# Me-RJ11_Adapter_v2_0.net
KiCad netlist of a schematic drawn in EAGLE
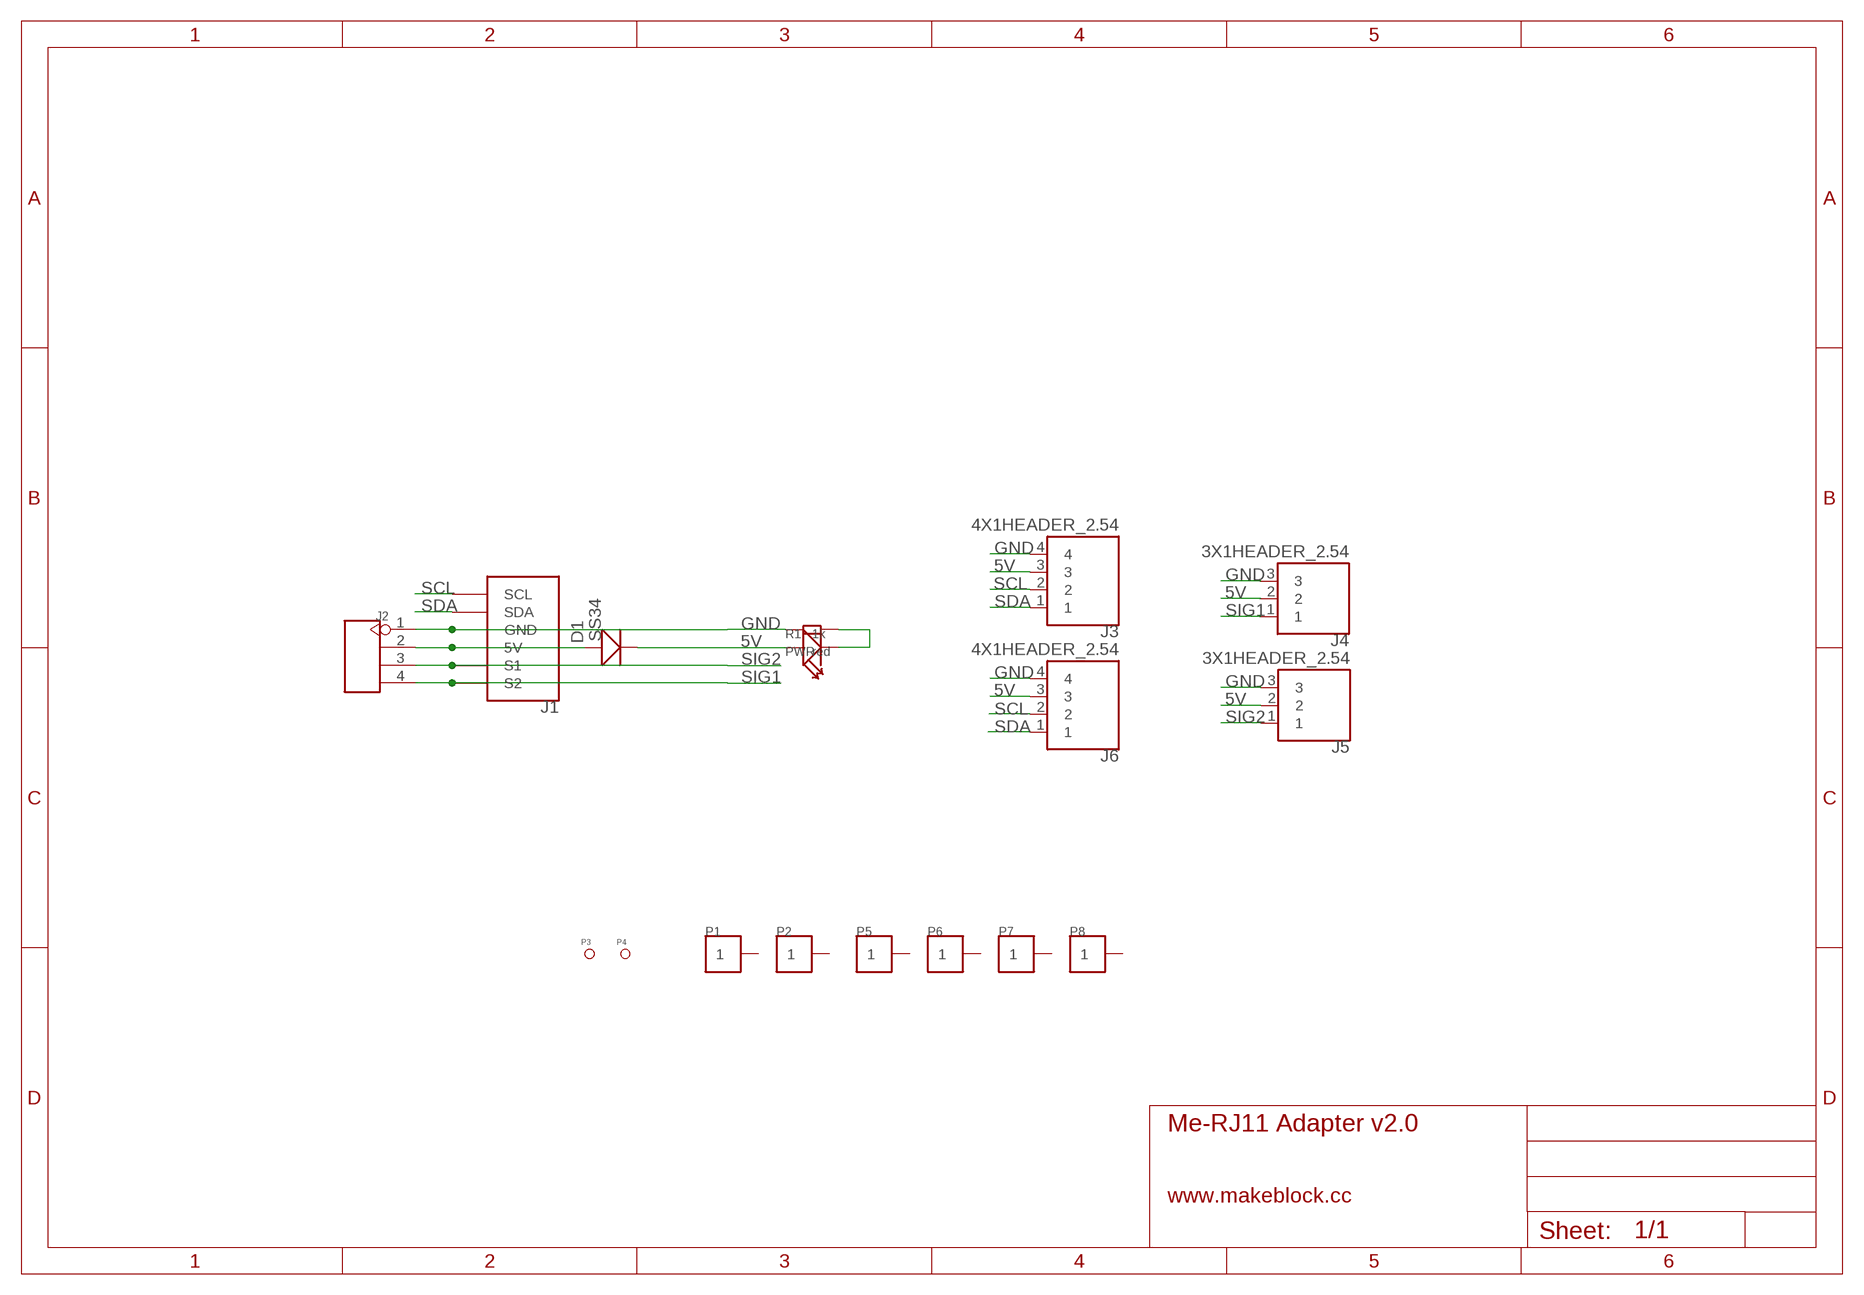
[diagram p0: schematic, sheet 1]

(export (version "E")
  (design (tool "Eeschema 10.0.6"))
  (components
    (comp (ref "D1")
      (value "SS34")
      (footprint "eagle-import:D2010")
      (libsource (lib "eagle-import") (part "D'SMA'"))
    )
    (comp (ref "J1")
      (value "RJ11-6P6C-DIGI")
      (footprint "eagle-import:RJ11-6P6C")
      (libsource (lib "eagle-import") (part "RJ11-6P6C-DIGI"))
    )
    (comp (ref "J2")
      (value "HEADER-4P-60/35MIL")
      (footprint "eagle-import:4P-65_35MIL")
      (libsource (lib "eagle-import") (part "HEADER-4P-60/35MIL"))
    )
    (comp (ref "J3")
      (value "4X1HEADER_2.54")
      (footprint "eagle-import:4X1HEADER_2.54")
      (libsource (lib "eagle-import") (part "4X1HEADER_2.54"))
    )
    (comp (ref "J4")
      (value "3X1HEADER_2.54")
      (footprint "eagle-import:3X1HEADER_2.54")
      (libsource (lib "eagle-import") (part "3X1HEADER_2.54"))
    )
    (comp (ref "J5")
      (value "3X1HEADER_2.54")
      (footprint "eagle-import:3X1HEADER_2.54")
      (libsource (lib "eagle-import") (part "3X1HEADER_2.54"))
    )
    (comp (ref "J6")
      (value "4X1HEADER_2.54")
      (footprint "eagle-import:4X1HEADER_2.54")
      (libsource (lib "eagle-import") (part "4X1HEADER_2.54"))
    )
    (comp (ref "P1")
      (value "PAD-1P-4MM")
      (footprint "eagle-import:HOLE-01")
      (libsource (lib "eagle-import") (part "PAD-1P-4MM"))
    )
    (comp (ref "P2")
      (value "PAD-1P-4MM")
      (footprint "eagle-import:HOLE-01")
      (libsource (lib "eagle-import") (part "PAD-1P-4MM"))
    )
    (comp (ref "P3")
      (value "PAD-MARK")
      (footprint "eagle-import:ROUND-MARK-1.0")
      (fields (field (name "PARTNO") "DNP"))
      (libsource (lib "eagle-import") (part "PAD-MARK"))
    )
    (comp (ref "P4")
      (value "PAD-MARK")
      (footprint "eagle-import:ROUND-MARK-1.0")
      (fields (field (name "PARTNO") "DNP"))
      (libsource (lib "eagle-import") (part "PAD-MARK"))
    )
    (comp (ref "P5")
      (value "PAD-1P-4MM")
      (footprint "eagle-import:HOLE-01")
      (libsource (lib "eagle-import") (part "PAD-1P-4MM"))
    )
    (comp (ref "P6")
      (value "PAD-1P-4MM")
      (footprint "eagle-import:HOLE-01")
      (libsource (lib "eagle-import") (part "PAD-1P-4MM"))
    )
    (comp (ref "P7")
      (value "PAD-1P-4MM")
      (footprint "eagle-import:HOLE-01")
      (libsource (lib "eagle-import") (part "PAD-1P-4MM"))
    )
    (comp (ref "P8")
      (value "PAD-1P-4MM")
      (footprint "eagle-import:HOLE-01")
      (libsource (lib "eagle-import") (part "PAD-1P-4MM"))
    )
    (comp (ref "PWR")
      (value "red")
      (footprint "eagle-import:LED-0603")
      (libsource (lib "eagle-import") (part "LED'0603'"))
    )
    (comp (ref "R1")
      (value "1k")
      (footprint "eagle-import:0603")
      (libsource (lib "eagle-import") (part "R-0603"))
    )
  )
  (nets
    (net (code "1") (name "/5V") (class "Default")
      (node (ref "D1") (pin "-") (pinfunction "-_-") (pintype "passive"))
      (node (ref "J3") (pin "3") (pinfunction "3_3") (pintype "bidirectional"))
      (node (ref "J4") (pin "2") (pinfunction "2_2") (pintype "bidirectional"))
      (node (ref "J5") (pin "2") (pinfunction "2_2") (pintype "bidirectional"))
      (node (ref "J6") (pin "3") (pinfunction "3_3") (pintype "bidirectional"))
      (node (ref "PWR") (pin "+") (pinfunction "+_+") (pintype "passive"))
    )
    (net (code "2") (name "/GND") (class "Default")
      (node (ref "J1") (pin "3") (pinfunction "GND_3") (pintype "bidirectional"))
      (node (ref "J2") (pin "1") (pinfunction "P$1_1") (pintype "bidirectional"))
      (node (ref "J3") (pin "4") (pinfunction "4_4") (pintype "bidirectional"))
      (node (ref "J4") (pin "3") (pinfunction "3_3") (pintype "bidirectional"))
      (node (ref "J5") (pin "3") (pinfunction "3_3") (pintype "bidirectional"))
      (node (ref "J6") (pin "4") (pinfunction "4_4") (pintype "bidirectional"))
      (node (ref "R1") (pin "1") (pinfunction "1_1") (pintype "passive"))
    )
    (net (code "3") (name "/SCL") (class "Default")
      (node (ref "J1") (pin "1") (pinfunction "SCL_1") (pintype "bidirectional"))
      (node (ref "J3") (pin "2") (pinfunction "2_2") (pintype "bidirectional"))
      (node (ref "J6") (pin "2") (pinfunction "2_2") (pintype "bidirectional"))
    )
    (net (code "4") (name "/SDA") (class "Default")
      (node (ref "J1") (pin "2") (pinfunction "SDA_2") (pintype "bidirectional"))
      (node (ref "J3") (pin "1") (pinfunction "1_1") (pintype "bidirectional"))
      (node (ref "J6") (pin "1") (pinfunction "1_1") (pintype "bidirectional"))
    )
    (net (code "5") (name "/SIG1") (class "Default")
      (node (ref "J1") (pin "6") (pinfunction "S2_6") (pintype "bidirectional"))
      (node (ref "J2") (pin "4") (pinfunction "P$4_4") (pintype "bidirectional"))
      (node (ref "J4") (pin "1") (pinfunction "1_1") (pintype "bidirectional"))
    )
    (net (code "6") (name "/SIG2") (class "Default")
      (node (ref "J1") (pin "5") (pinfunction "S1_5") (pintype "bidirectional"))
      (node (ref "J2") (pin "3") (pinfunction "P$3_3") (pintype "bidirectional"))
      (node (ref "J5") (pin "1") (pinfunction "1_1") (pintype "bidirectional"))
    )
    (net (code "7") (name "Net-(J1-5V)") (class "Default")
      (node (ref "D1") (pin "+") (pinfunction "+_+") (pintype "passive"))
      (node (ref "J1") (pin "4") (pinfunction "5V_4") (pintype "bidirectional"))
      (node (ref "J2") (pin "2") (pinfunction "P$2_2") (pintype "bidirectional"))
    )
    (net (code "8") (name "Net-(PWR-Pad-)") (class "Default")
      (node (ref "PWR") (pin "-") (pinfunction "-_-") (pintype "passive"))
      (node (ref "R1") (pin "2") (pinfunction "2_2") (pintype "passive"))
    )
    (net (code "9") (name "unconnected-(P1-Pad1)") (class "Default")
      (node (ref "P1") (pin "1") (pinfunction "1_1") (pintype "bidirectional"))
    )
    (net (code "10") (name "unconnected-(P2-Pad1)") (class "Default")
      (node (ref "P2") (pin "1") (pinfunction "1_1") (pintype "bidirectional"))
    )
    (net (code "11") (name "unconnected-(P5-Pad1)") (class "Default")
      (node (ref "P5") (pin "1") (pinfunction "1_1") (pintype "bidirectional"))
    )
    (net (code "12") (name "unconnected-(P6-Pad1)") (class "Default")
      (node (ref "P6") (pin "1") (pinfunction "1_1") (pintype "bidirectional"))
    )
    (net (code "13") (name "unconnected-(P7-Pad1)") (class "Default")
      (node (ref "P7") (pin "1") (pinfunction "1_1") (pintype "bidirectional"))
    )
    (net (code "14") (name "unconnected-(P8-Pad1)") (class "Default")
      (node (ref "P8") (pin "1") (pinfunction "1_1") (pintype "bidirectional"))
    )
  )
)
